# rs485.net
KiCad netlist of a schematic drawn in EAGLE
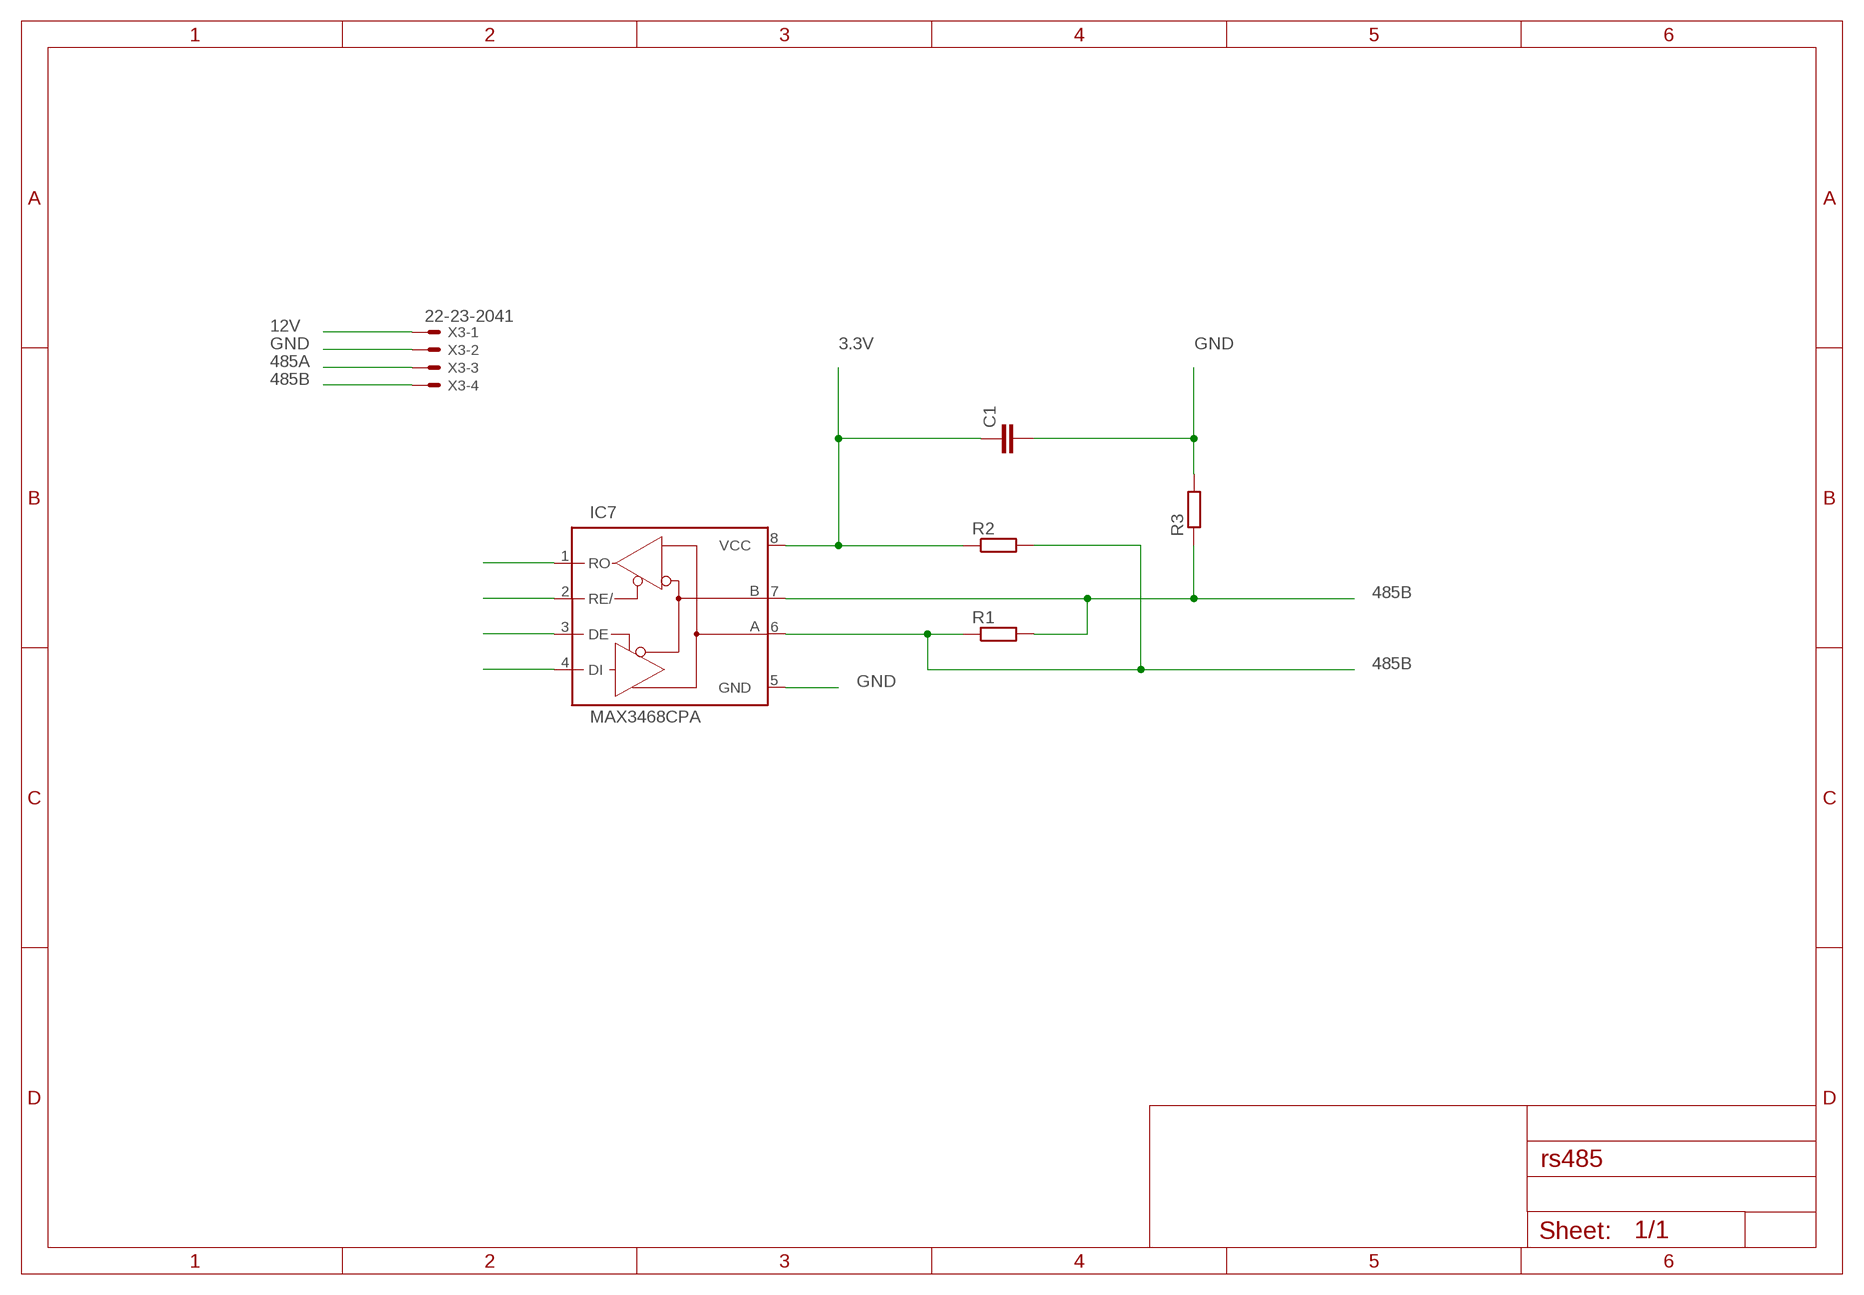
[diagram p0: schematic, sheet 1]

(export (version "E")
  (design (tool "Eeschema 10.0.6"))
  (components
    (comp (ref "C1")
      (value "C-EU025-024X044")
      (footprint "eagle-import:C025-024X044")
      (libsource (lib "eagle-import") (part "C-EU025-024X044"))
    )
    (comp (ref "IC7")
      (value "MAX3468CPA")
      (footprint "eagle-import:DIL08")
      (libsource (lib "eagle-import") (part "MAX34PA68C"))
    )
    (comp (ref "R1")
      (value "R-EU_0207/10")
      (footprint "eagle-import:0207_10")
      (libsource (lib "eagle-import") (part "R-EU_0207/10"))
    )
    (comp (ref "R2")
      (value "R-EU_0207/10")
      (footprint "eagle-import:0207_10")
      (libsource (lib "eagle-import") (part "R-EU_0207/10"))
    )
    (comp (ref "R3")
      (value "R-EU_0207/10")
      (footprint "eagle-import:0207_10")
      (libsource (lib "eagle-import") (part "R-EU_0207/10"))
    )
    (comp (ref "X3")
      (value "22-23-2041")
      (footprint "eagle-import:22-23-2041")
      (fields (field (name "MF") "MOLEX"))
      (libsource (lib "eagle-import") (part "22-23-2041"))
    )
  )
  (nets
    (net (code "1") (name "/3.3V") (class "Default")
      (node (ref "C1") (pin "1") (pinfunction "1_1") (pintype "passive"))
      (node (ref "IC7") (pin "8") (pinfunction "VCC_8") (pintype "power_in"))
      (node (ref "R2") (pin "1") (pinfunction "1_1") (pintype "passive"))
    )
    (net (code "2") (name "/12V") (class "Default")
      (node (ref "X3") (pin "1") (pinfunction "S_1") (pintype "passive"))
    )
    (net (code "3") (name "/485A") (class "Default")
      (node (ref "X3") (pin "3") (pinfunction "S_3") (pintype "passive"))
    )
    (net (code "4") (name "/485B") (class "Default")
      (node (ref "IC7") (pin "6") (pinfunction "A_6") (pintype "passive"))
      (node (ref "IC7") (pin "7") (pinfunction "B_7") (pintype "passive"))
      (node (ref "R1") (pin "1") (pinfunction "1_1") (pintype "passive"))
      (node (ref "R1") (pin "2") (pinfunction "2_2") (pintype "passive"))
      (node (ref "R2") (pin "2") (pinfunction "2_2") (pintype "passive"))
      (node (ref "R3") (pin "1") (pinfunction "1_1") (pintype "passive"))
      (node (ref "X3") (pin "4") (pinfunction "S_4") (pintype "passive"))
    )
    (net (code "5") (name "/GND") (class "Default")
      (node (ref "C1") (pin "2") (pinfunction "2_2") (pintype "passive"))
      (node (ref "IC7") (pin "5") (pinfunction "GND_5") (pintype "power_in"))
      (node (ref "R3") (pin "2") (pinfunction "2_2") (pintype "passive"))
      (node (ref "X3") (pin "2") (pinfunction "S_2") (pintype "passive"))
    )
    (net (code "6") (name "unconnected-(IC7-DE-Pad3)") (class "Default")
      (node (ref "IC7") (pin "3") (pinfunction "DE_3") (pintype "input"))
    )
    (net (code "7") (name "unconnected-(IC7-DI-Pad4)") (class "Default")
      (node (ref "IC7") (pin "4") (pinfunction "DI_4") (pintype "input"))
    )
    (net (code "8") (name "unconnected-(IC7-RE{slash}-Pad2)") (class "Default")
      (node (ref "IC7") (pin "2") (pinfunction "RE/_2") (pintype "input"))
    )
    (net (code "9") (name "unconnected-(IC7-RO-Pad1)") (class "Default")
      (node (ref "IC7") (pin "1") (pinfunction "RO_1") (pintype "output"))
    )
  )
)
